# MCORD_SAS_BNC.net
KiCad netlist of a schematic drawn in Altium Designer
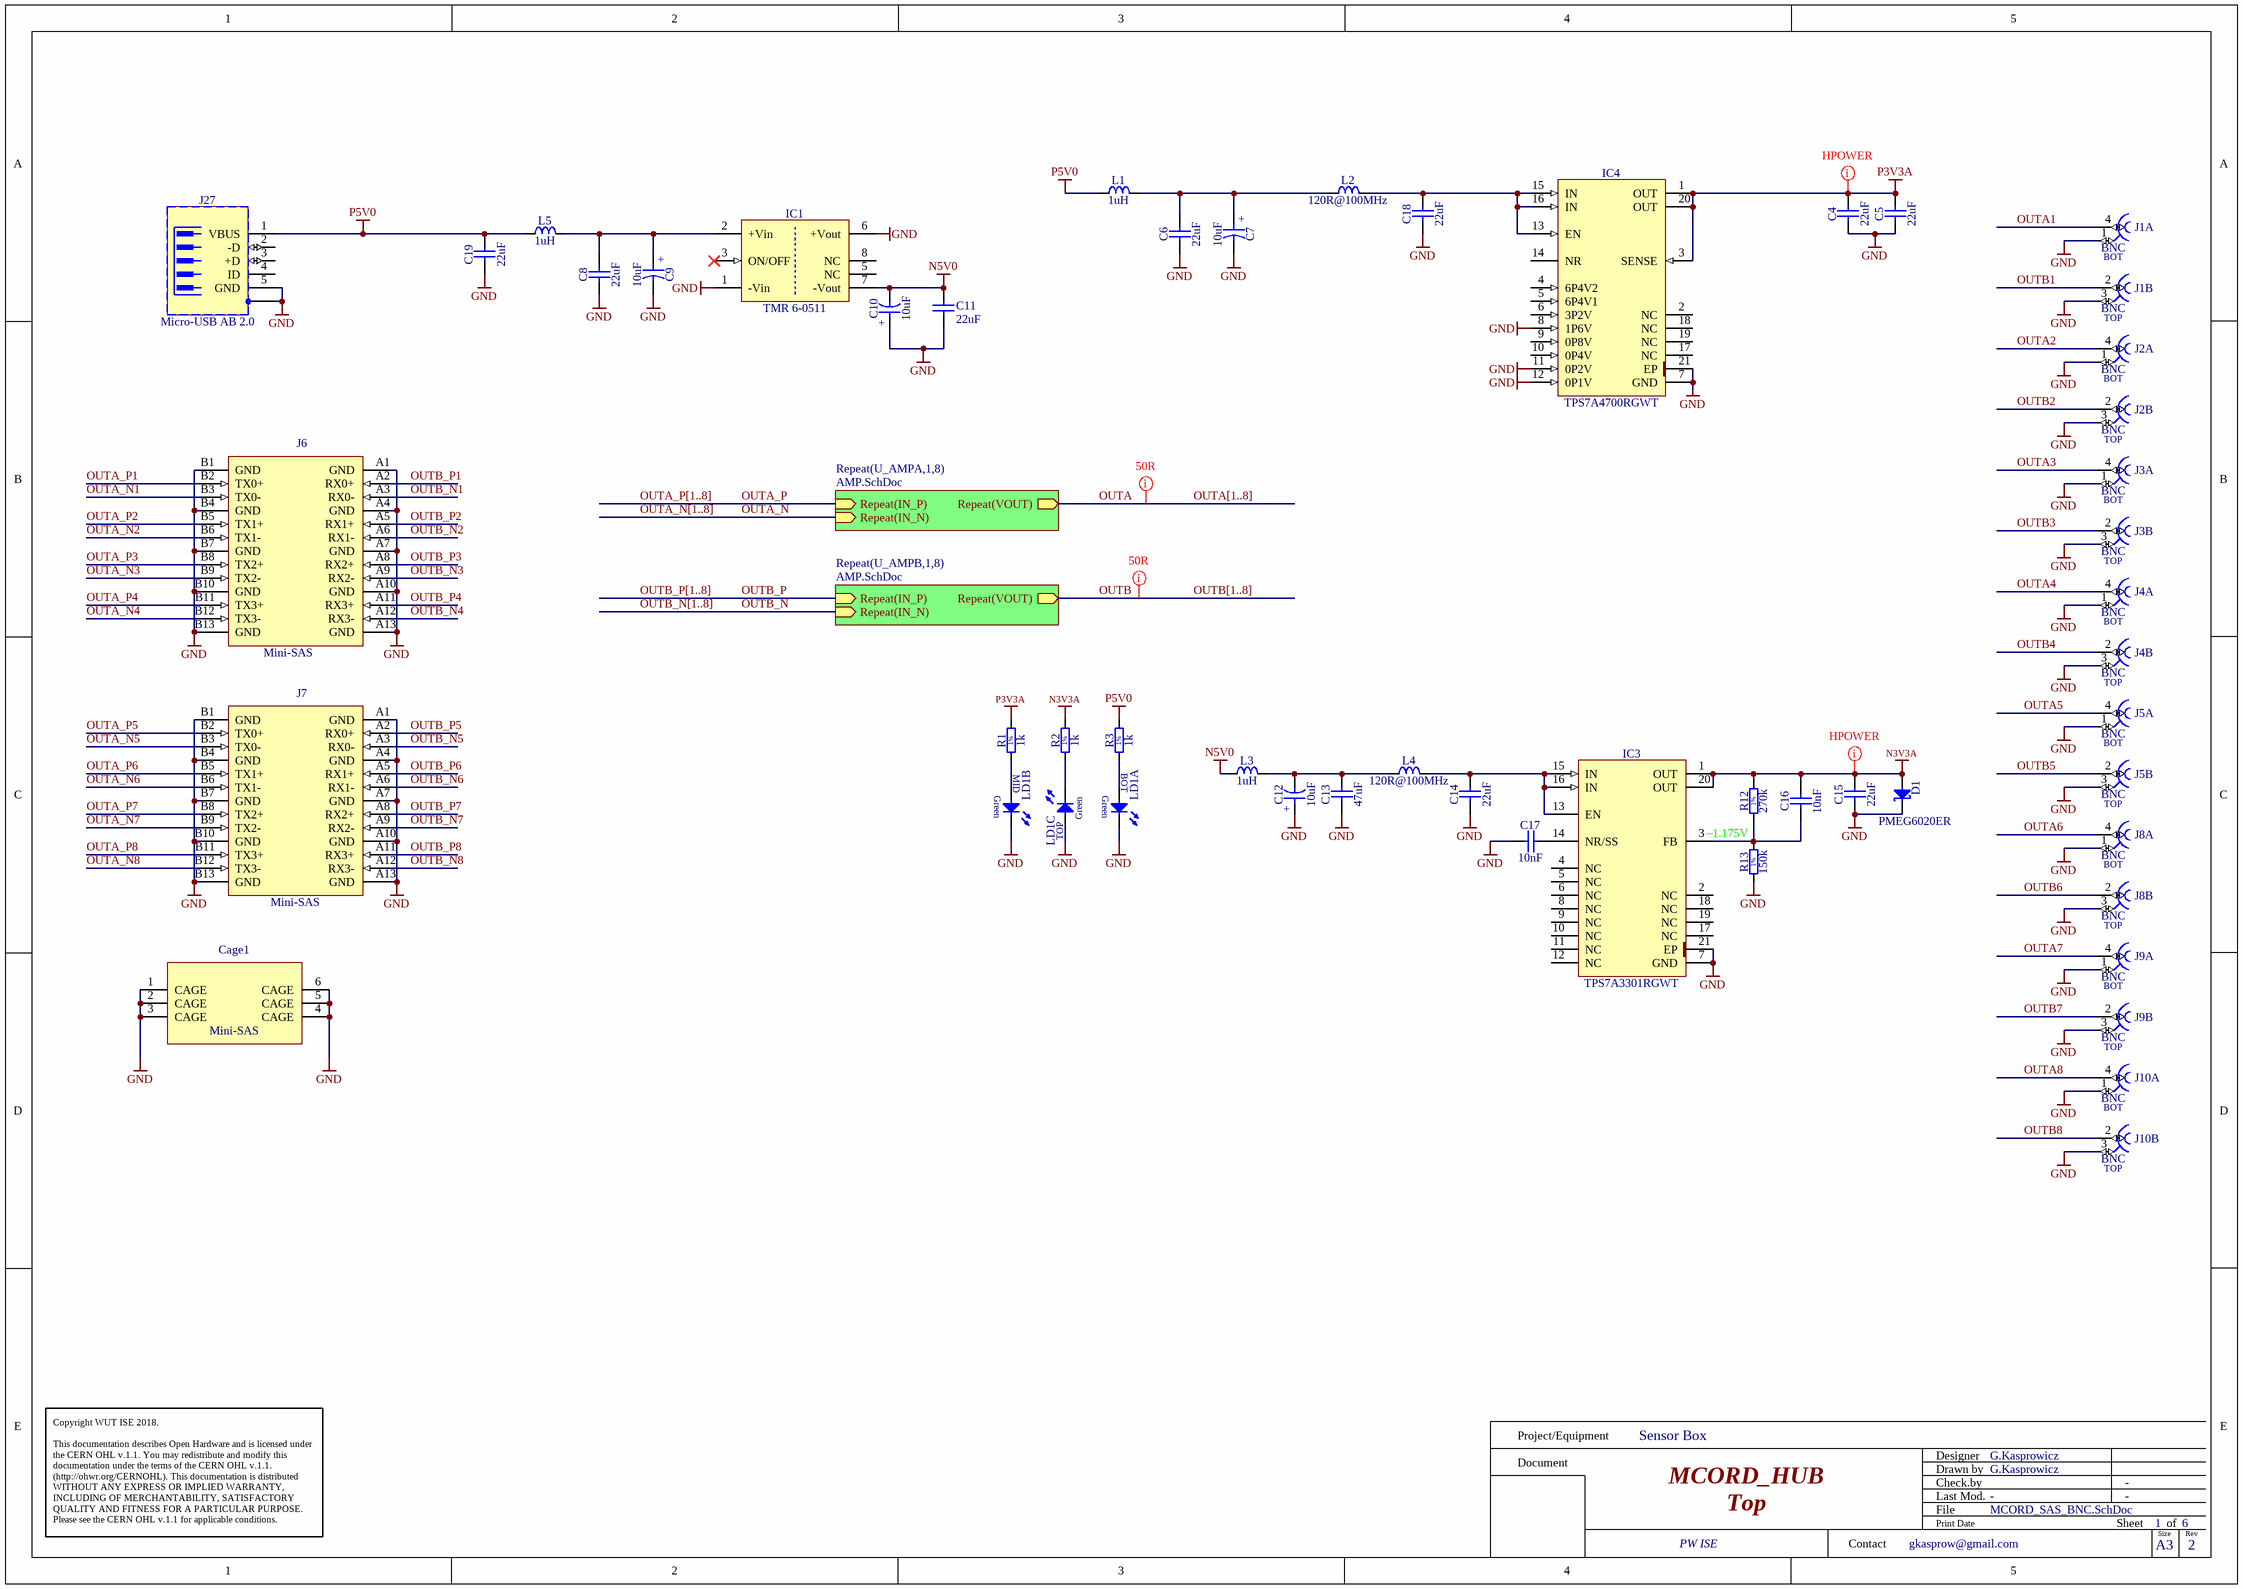
[diagram p0: MCORD_SAS_BNC.SchDoc]

(export (version "E")
  (design (tool "Eeschema 10.0.6"))
  (components
    (comp (ref "C4")
      (value "22uF")
      (footprint "CAPC2012X135N")
      (description "Non-polarised capacitor")
      (fields
        (field (name "PART NUMBER") "CC0805_22UF_16V_10%_X5R")
        (field (name "VOLTAGE") "16V")
        (field (name "AUTHOR") "CERN DEM JLC")
      )
      (libsource (lib "Capacitors") (part "Capacitor - non polarized"))
    )
    (comp (ref "C5")
      (value "22uF")
      (footprint "CAPC2012X135N")
      (description "Non-polarised capacitor")
      (fields
        (field (name "PART NUMBER") "CC0805_22UF_16V_10%_X5R")
        (field (name "VOLTAGE") "16V")
        (field (name "AUTHOR") "CERN DEM JLC")
      )
      (libsource (lib "Capacitors") (part "Capacitor - non polarized"))
    )
    (comp (ref "C6")
      (value "22uF")
      (footprint "CAPC2012X135N")
      (description "Non-polarised capacitor")
      (fields
        (field (name "PART NUMBER") "CC0805_22UF_16V_10%_X5R")
        (field (name "VOLTAGE") "16V")
        (field (name "AUTHOR") "CERN DEM JLC")
      )
      (libsource (lib "Capacitors") (part "Capacitor - non polarized"))
    )
    (comp (ref "C7")
      (value "10uF")
      (footprint "CAPMP3216X180N")
      (description "Polarised capacitor")
      (fields
        (field (name "PART NUMBER") "CTE3216-18_10UF_10V_10%_LESR1800")
        (field (name "VOLTAGE") "10V")
        (field (name "AUTHOR") "CERN DEM JLC")
      )
      (libsource (lib "Capacitors") (part "Capacitor - polarized"))
    )
    (comp (ref "C8")
      (value "22uF")
      (footprint "CAPC2012X135N")
      (description "Non-polarised capacitor")
      (fields
        (field (name "PART NUMBER") "CC0805_22UF_16V_10%_X5R")
        (field (name "VOLTAGE") "16V")
        (field (name "AUTHOR") "CERN DEM JLC")
      )
      (libsource (lib "Capacitors") (part "Capacitor - non polarized"))
    )
    (comp (ref "C9")
      (value "10uF")
      (footprint "CAPMP3216X180N")
      (description "Polarised capacitor")
      (fields
        (field (name "PART NUMBER") "CTE3216-18_10UF_10V_10%_LESR1800")
        (field (name "VOLTAGE") "10V")
        (field (name "AUTHOR") "CERN DEM JLC")
      )
      (libsource (lib "Capacitors") (part "Capacitor - polarized"))
    )
    (comp (ref "C10")
      (value "10uF")
      (footprint "CAPMP3216X180N")
      (description "Polarised capacitor")
      (fields
        (field (name "PART NUMBER") "CTE3216-18_10UF_10V_10%_LESR1800")
        (field (name "VOLTAGE") "10V")
        (field (name "AUTHOR") "CERN DEM JLC")
      )
      (libsource (lib "Capacitors") (part "Capacitor - polarized"))
    )
    (comp (ref "C11")
      (value "22uF")
      (footprint "CAPC2012X135N")
      (description "Non-polarised capacitor")
      (fields
        (field (name "PART NUMBER") "CC0805_22UF_16V_10%_X5R")
        (field (name "VOLTAGE") "16V")
        (field (name "AUTHOR") "CERN DEM JLC")
      )
      (libsource (lib "Capacitors") (part "Capacitor - non polarized"))
    )
    (comp (ref "C12")
      (value "10uF")
      (footprint "CAPMP3216X180N")
      (description "Polarised capacitor")
      (fields
        (field (name "PART NUMBER") "CTE3216-18_10UF_10V_10%_LESR1800")
        (field (name "VOLTAGE") "10V")
        (field (name "AUTHOR") "CERN DEM JLC")
      )
      (libsource (lib "Capacitors") (part "Capacitor - polarized"))
    )
    (comp (ref "C13")
      (value "47uF")
      (footprint "CAPC2012X140N")
      (description "Non-polarised capacitor")
      (fields
        (field (name "PART NUMBER") "CC0805_47UF_6.3V_20%_X5R")
        (field (name "VOLTAGE") "6.3V")
        (field (name "AUTHOR") "CERN DEM JLC")
      )
      (libsource (lib "Capacitors") (part "Capacitor - non polarized"))
    )
    (comp (ref "C14")
      (value "22uF")
      (footprint "CAPC2012X135N")
      (description "Non-polarised capacitor")
      (fields
        (field (name "PART NUMBER") "CC0805_22UF_16V_10%_X5R")
        (field (name "VOLTAGE") "16V")
        (field (name "AUTHOR") "CERN DEM JLC")
      )
      (libsource (lib "Capacitors") (part "Capacitor - non polarized"))
    )
    (comp (ref "C15")
      (value "22uF")
      (footprint "CAPC2012X135N")
      (description "Non-polarised capacitor")
      (fields
        (field (name "PART NUMBER") "CC0805_22UF_16V_10%_X5R")
        (field (name "VOLTAGE") "16V")
        (field (name "AUTHOR") "CERN DEM JLC")
      )
      (libsource (lib "Capacitors") (part "Capacitor - non polarized"))
    )
    (comp (ref "C16")
      (value "10nF")
      (footprint "CAPC1608X87N")
      (description "Non-polarised capacitor")
      (fields
        (field (name "PART NUMBER") "CC0603_10NF_50V_10%_X7R")
        (field (name "VOLTAGE") "50V")
        (field (name "AUTHOR") "CERN DEM JLC")
      )
      (libsource (lib "Capacitors") (part "Capacitor - non polarized"))
    )
    (comp (ref "C17")
      (value "10nF")
      (footprint "CAPC1608X87N")
      (description "Non-polarised capacitor")
      (fields
        (field (name "PART NUMBER") "CC0603_10NF_50V_10%_X7R")
        (field (name "VOLTAGE") "50V")
        (field (name "AUTHOR") "CERN DEM JLC")
      )
      (libsource (lib "Capacitors") (part "Capacitor - non polarized"))
    )
    (comp (ref "C18")
      (value "22uF")
      (footprint "CAPC2012X135N")
      (description "Non-polarised capacitor")
      (fields
        (field (name "PART NUMBER") "CC0805_22UF_16V_10%_X5R")
        (field (name "VOLTAGE") "16V")
        (field (name "AUTHOR") "CERN DEM JLC")
      )
      (libsource (lib "Capacitors") (part "Capacitor - non polarized"))
    )
    (comp (ref "C19")
      (value "22uF")
      (footprint "CAPC2012X135N")
      (description "Non-polarised capacitor")
      (fields
        (field (name "PART NUMBER") "CC0805_22UF_16V_10%_X5R")
        (field (name "VOLTAGE") "16V")
        (field (name "AUTHOR") "CERN DEM JLC")
      )
      (libsource (lib "Capacitors") (part "Capacitor - non polarized"))
    )
    (comp (ref "Cage1")
      (value "Mini-SAS")
      (footprint "TYCO_1888321-2")
      (description "Mini-SAS Cage (6Pins)")
      (fields
        (field (name "PART NUMBER") "TYCO_1888321-2")
        (field (name "MANUFACTURER") "TYCO ELECTRONICS")
        (field (name "AUTHOR") "CERN DEM BC")
      )
      (libsource (lib "Connectors") (part "Mini-SAS Cage (6Pins)"))
    )
    (comp (ref "D1")
      (value "PMEG6020ER")
      (footprint "SODFL3517X110N")
      (description "Schottky Diode")
      (fields
        (field (name "VOLTAGE") "60V")
        (field (name "POWER") "2A")
        (field (name "AUTHOR") "CERN DEM JMW")
      )
      (libsource (lib "ICs And Semiconductors") (part "Diode Schottky"))
    )
    (comp (ref "IC1")
      (value "TMR 6-0511")
      (footprint "DCDC_TRACO_TMR6")
      (description "TRACO, TMR Series, Single Output DCDC Converter")
      (fields (field (name "MANUFACTURER") "TRACO POWER") (field (name "AUTHOR") "CERN DEM MR"))
      (libsource (lib "ICs And Semiconductors") (part "DCDC_TRACO_TMR_Single Output"))
    )
    (comp (ref "IC3")
      (value "TPS7A3301RGWT")
      (footprint "QFN65P500X500X100-21N-S325")
      (description "-1.18V to -33V -1A, Ultra-Low Noise, High PSRR, Low-Dropout Linear Regulator")
      (fields (field (name "MANUFACTURER") "TEXAS INSTRUMENTS") (field (name "AUTHOR") "CERN DEM JLC"))
      (libsource (lib "ICs And Semiconductors") (part "TPS7A3301RGW"))
    )
    (comp (ref "IC4")
      (value "TPS7A4700RGWT")
      (footprint "QFN65P500X500X100-21N-S325")
      (description "Low Noise (3uVrms), 1A, High Voltage Low-Dropout Linear Regulator")
      (fields (field (name "MANUFACTURER") "TEXAS INSTRUMENTS") (field (name "AUTHOR") "CERN DEM JLC"))
      (libsource (lib "ICs And Semiconductors") (part "TPS7A4700RGW"))
    )
    (comp (ref "J1")
      (value "BNC")
      (footprint "BOMAR_364A2595")
      (description "Dual Right Angle 50 Ohm BNC Jack, White Valox Case")
      (fields
        (field (name "PART NUMBER") "BOMAR_364A2595")
        (field (name "MANUFACTURER") "BOMAR INTERCONNECT")
        (field (name "AUTHOR") "CERN DEM JLC")
      )
      (libsource (lib "Connectors") (part "BOMAR_364A2595"))
    )
    (comp (ref "J2")
      (value "BNC")
      (footprint "BOMAR_364A2595")
      (description "Dual Right Angle 50 Ohm BNC Jack, White Valox Case")
      (fields
        (field (name "PART NUMBER") "BOMAR_364A2595")
        (field (name "MANUFACTURER") "BOMAR INTERCONNECT")
        (field (name "AUTHOR") "CERN DEM JLC")
      )
      (libsource (lib "Connectors") (part "BOMAR_364A2595"))
    )
    (comp (ref "J3")
      (value "BNC")
      (footprint "BOMAR_364A2595")
      (description "Dual Right Angle 50 Ohm BNC Jack, White Valox Case")
      (fields
        (field (name "PART NUMBER") "BOMAR_364A2595")
        (field (name "MANUFACTURER") "BOMAR INTERCONNECT")
        (field (name "AUTHOR") "CERN DEM JLC")
      )
      (libsource (lib "Connectors") (part "BOMAR_364A2595"))
    )
    (comp (ref "J4")
      (value "BNC")
      (footprint "BOMAR_364A2595")
      (description "Dual Right Angle 50 Ohm BNC Jack, White Valox Case")
      (fields
        (field (name "PART NUMBER") "BOMAR_364A2595")
        (field (name "MANUFACTURER") "BOMAR INTERCONNECT")
        (field (name "AUTHOR") "CERN DEM JLC")
      )
      (libsource (lib "Connectors") (part "BOMAR_364A2595"))
    )
    (comp (ref "J5")
      (value "BNC")
      (footprint "BOMAR_364A2595")
      (description "Dual Right Angle 50 Ohm BNC Jack, White Valox Case")
      (fields
        (field (name "PART NUMBER") "BOMAR_364A2595")
        (field (name "MANUFACTURER") "BOMAR INTERCONNECT")
        (field (name "AUTHOR") "CERN DEM JLC")
      )
      (libsource (lib "Connectors") (part "BOMAR_364A2595"))
    )
    (comp (ref "J6")
      (value "Mini-SAS")
      (footprint "TYCO_1761987-7")
      (description "26 Position Mini-Sas Connector (Quad Small Form-Factor SFF-8088)")
      (fields
        (field (name "PART NUMBER") "TYCO_1761987-7")
        (field (name "MANUFACTURER") "TYCO ELECTRONICS")
        (field (name "AUTHOR") "CERN DEM MR")
      )
      (libsource (lib "Connectors") (part "Mini-SAS"))
    )
    (comp (ref "J7")
      (value "Mini-SAS")
      (footprint "TYCO_1761987-7")
      (description "26 Position Mini-Sas Connector (Quad Small Form-Factor SFF-8088)")
      (fields
        (field (name "PART NUMBER") "TYCO_1761987-7")
        (field (name "MANUFACTURER") "TYCO ELECTRONICS")
        (field (name "AUTHOR") "CERN DEM MR")
      )
      (libsource (lib "Connectors") (part "Mini-SAS"))
    )
    (comp (ref "J8")
      (value "BNC")
      (footprint "BOMAR_364A2595")
      (description "Dual Right Angle 50 Ohm BNC Jack, White Valox Case")
      (fields
        (field (name "PART NUMBER") "BOMAR_364A2595")
        (field (name "MANUFACTURER") "BOMAR INTERCONNECT")
        (field (name "AUTHOR") "CERN DEM JLC")
      )
      (libsource (lib "Connectors") (part "BOMAR_364A2595"))
    )
    (comp (ref "J9")
      (value "BNC")
      (footprint "BOMAR_364A2595")
      (description "Dual Right Angle 50 Ohm BNC Jack, White Valox Case")
      (fields
        (field (name "PART NUMBER") "BOMAR_364A2595")
        (field (name "MANUFACTURER") "BOMAR INTERCONNECT")
        (field (name "AUTHOR") "CERN DEM JLC")
      )
      (libsource (lib "Connectors") (part "BOMAR_364A2595"))
    )
    (comp (ref "J10")
      (value "BNC")
      (footprint "BOMAR_364A2595")
      (description "Dual Right Angle 50 Ohm BNC Jack, White Valox Case")
      (fields
        (field (name "PART NUMBER") "BOMAR_364A2595")
        (field (name "MANUFACTURER") "BOMAR INTERCONNECT")
        (field (name "AUTHOR") "CERN DEM JLC")
      )
      (libsource (lib "Connectors") (part "BOMAR_364A2595"))
    )
    (comp (ref "J27")
      (value "Micro-USB AB 2.0")
      (footprint "HIROSE_ZX62RD-AB-5P8(30)")
      (description "5 Pin + 1 Shield USB Receptacle")
      (fields
        (field (name "PART NUMBER") "HIROSE_ZX62RD-AB-5P8(30)")
        (field (name "MANUFACTURER") "HIROSE (HRS)")
        (field (name "AUTHOR") "CERN DEM JMW")
      )
      (libsource (lib "Connectors") (part "Connector USB 5 Pin + 1Shield"))
    )
    (comp (ref "L1")
      (value "1uH")
      (footprint "INDC2620X100N")
      (description "Inductor")
      (fields
        (field (name "PART NUMBER") "IND1008_1UH_20%_WURTH_74479787210B")
        (field (name "POWER") "1.95A")
        (field (name "AUTHOR") "CERN DEM JLC")
      )
      (libsource (lib "Inductors & Transformers") (part "Inductor"))
    )
    (comp (ref "L2")
      (value "120R@100MHz")
      (footprint "INDC1608X65N")
      (description "Inductor")
      (fields
        (field (name "PART NUMBER") "IND0603_MURATA_BLM18SG121TN1D")
        (field (name "POWER") "3A")
        (field (name "AUTHOR") "CERN DEM JLC")
      )
      (libsource (lib "Inductors & Transformers") (part "Inductor"))
    )
    (comp (ref "L3")
      (value "1uH")
      (footprint "INDC2620X100N")
      (description "Inductor")
      (fields
        (field (name "PART NUMBER") "IND1008_1UH_20%_WURTH_74479787210B")
        (field (name "POWER") "1.95A")
        (field (name "AUTHOR") "CERN DEM JLC")
      )
      (libsource (lib "Inductors & Transformers") (part "Inductor"))
    )
    (comp (ref "L4")
      (value "120R@100MHz")
      (footprint "INDC1608X65N")
      (description "Inductor")
      (fields
        (field (name "PART NUMBER") "IND0603_MURATA_BLM18SG121TN1D")
        (field (name "POWER") "3A")
        (field (name "AUTHOR") "CERN DEM JLC")
      )
      (libsource (lib "Inductors & Transformers") (part "Inductor"))
    )
    (comp (ref "L5")
      (value "1uH")
      (footprint "INDC2620X100N")
      (description "Inductor")
      (fields
        (field (name "PART NUMBER") "IND1008_1UH_20%_WURTH_74479787210B")
        (field (name "POWER") "1.95A")
        (field (name "AUTHOR") "CERN DEM JLC")
      )
      (libsource (lib "Inductors & Transformers") (part "Inductor"))
    )
    (comp (ref "LD1")
      (value "Green/Green/Green")
      (footprint "LED_DIALIGHT_570-0100-222F")
      (description "LED x3 Green LED")
      (fields
        (field (name "PART NUMBER") "LED_DIALIGHT_570-0100-222F")
        (field (name "MANUFACTURER") "DIALIGHT")
        (field (name "AUTHOR") "CERN DEM JLC")
      )
      (libsource (lib "ICs And Semiconductors") (part "LED x3 G-1A2C-BOT_G-3A4C_G-5A6C-TOP"))
    )
    (comp (ref "R1")
      (value "1k")
      (footprint "RESC1608X55N")
      (description "Resistor - 1%")
      (fields
        (field (name "PART NUMBER") "R0603_1K_1%_0.1W_100PPM")
        (field (name "POWER") "0.1W")
        (field (name "AUTHOR") "CERN DEM JLC")
      )
      (libsource (lib "Resistors") (part "Resistor - 1%"))
    )
    (comp (ref "R2")
      (value "1k")
      (footprint "RESC1608X55N")
      (description "Resistor - 1%")
      (fields
        (field (name "PART NUMBER") "R0603_1K_1%_0.1W_100PPM")
        (field (name "POWER") "0.1W")
        (field (name "AUTHOR") "CERN DEM JLC")
      )
      (libsource (lib "Resistors") (part "Resistor - 1%"))
    )
    (comp (ref "R3")
      (value "1k")
      (footprint "RESC1608X55N")
      (description "Resistor - 1%")
      (fields
        (field (name "PART NUMBER") "R0603_1K_1%_0.1W_100PPM")
        (field (name "POWER") "0.1W")
        (field (name "AUTHOR") "CERN DEM JLC")
      )
      (libsource (lib "Resistors") (part "Resistor - 1%"))
    )
    (comp (ref "R12")
      (value "270k")
      (footprint "RESC1608X55N")
      (description "Resistor - 1%")
      (fields
        (field (name "PART NUMBER") "R0603_270K_1%_0.1W_100PPM")
        (field (name "POWER") "0.1W")
        (field (name "AUTHOR") "CERN DEM JLC")
      )
      (libsource (lib "Resistors") (part "Resistor - 1%"))
    )
    (comp (ref "R13")
      (value "150k")
      (footprint "RESC1608X55N")
      (description "Resistor - 1%")
      (fields
        (field (name "PART NUMBER") "R0603_150K_1%_0.1W_100PPM")
        (field (name "POWER") "0.1W")
        (field (name "AUTHOR") "CERN DEM JLC")
      )
      (libsource (lib "Resistors") (part "Resistor - 1%"))
    )
  )
  (nets
    (net (code "2") (name "/OUTA1") (class "Default")
      (node (ref "J1") (pin "4") (pinfunction "4_4") (pintype "bidirectional"))
    )
    (net (code "3") (name "/OUTA2") (class "Default")
      (node (ref "J2") (pin "4") (pinfunction "4_4") (pintype "bidirectional"))
    )
    (net (code "4") (name "/OUTA3") (class "Default")
      (node (ref "J3") (pin "4") (pinfunction "4_4") (pintype "bidirectional"))
    )
    (net (code "5") (name "/OUTA4") (class "Default")
      (node (ref "J4") (pin "4") (pinfunction "4_4") (pintype "bidirectional"))
    )
    (net (code "6") (name "/OUTA5") (class "Default")
      (node (ref "J5") (pin "4") (pinfunction "4_4") (pintype "bidirectional"))
    )
    (net (code "7") (name "/OUTA6") (class "Default")
      (node (ref "J8") (pin "4") (pinfunction "4_4") (pintype "bidirectional"))
    )
    (net (code "8") (name "/OUTA7") (class "Default")
      (node (ref "J9") (pin "4") (pinfunction "4_4") (pintype "bidirectional"))
    )
    (net (code "9") (name "/OUTA8") (class "Default")
      (node (ref "J10") (pin "4") (pinfunction "4_4") (pintype "bidirectional"))
    )
    (net (code "12") (name "/OUTA_N1") (class "Default")
      (node (ref "J6") (pin "B3") (pinfunction "TX0-_B3") (pintype "input"))
    )
    (net (code "13") (name "/OUTA_N2") (class "Default")
      (node (ref "J6") (pin "B6") (pinfunction "TX1-_B6") (pintype "input"))
    )
    (net (code "14") (name "/OUTA_N3") (class "Default")
      (node (ref "J6") (pin "B9") (pinfunction "TX2-_B9") (pintype "input"))
    )
    (net (code "15") (name "/OUTA_N4") (class "Default")
      (node (ref "J6") (pin "B12") (pinfunction "TX3-_B12") (pintype "input"))
    )
    (net (code "16") (name "/OUTA_N5") (class "Default")
      (node (ref "J7") (pin "B3") (pinfunction "TX0-_B3") (pintype "input"))
    )
    (net (code "17") (name "/OUTA_N6") (class "Default")
      (node (ref "J7") (pin "B6") (pinfunction "TX1-_B6") (pintype "input"))
    )
    (net (code "18") (name "/OUTA_N7") (class "Default")
      (node (ref "J7") (pin "B9") (pinfunction "TX2-_B9") (pintype "input"))
    )
    (net (code "19") (name "/OUTA_N8") (class "Default")
      (node (ref "J7") (pin "B12") (pinfunction "TX3-_B12") (pintype "input"))
    )
    (net (code "22") (name "/OUTA_P1") (class "Default")
      (node (ref "J6") (pin "B2") (pinfunction "TX0+_B2") (pintype "input"))
    )
    (net (code "23") (name "/OUTA_P2") (class "Default")
      (node (ref "J6") (pin "B5") (pinfunction "TX1+_B5") (pintype "input"))
    )
    (net (code "24") (name "/OUTA_P3") (class "Default")
      (node (ref "J6") (pin "B8") (pinfunction "TX2+_B8") (pintype "input"))
    )
    (net (code "25") (name "/OUTA_P4") (class "Default")
      (node (ref "J6") (pin "B11") (pinfunction "TX3+_B11") (pintype "input"))
    )
    (net (code "26") (name "/OUTA_P5") (class "Default")
      (node (ref "J7") (pin "B2") (pinfunction "TX0+_B2") (pintype "input"))
    )
    (net (code "27") (name "/OUTA_P6") (class "Default")
      (node (ref "J7") (pin "B5") (pinfunction "TX1+_B5") (pintype "input"))
    )
    (net (code "28") (name "/OUTA_P7") (class "Default")
      (node (ref "J7") (pin "B8") (pinfunction "TX2+_B8") (pintype "input"))
    )
    (net (code "29") (name "/OUTA_P8") (class "Default")
      (node (ref "J7") (pin "B11") (pinfunction "TX3+_B11") (pintype "input"))
    )
    (net (code "32") (name "/OUTB1") (class "Default")
      (node (ref "J1") (pin "2") (pinfunction "2_2") (pintype "bidirectional"))
    )
    (net (code "33") (name "/OUTB2") (class "Default")
      (node (ref "J2") (pin "2") (pinfunction "2_2") (pintype "bidirectional"))
    )
    (net (code "34") (name "/OUTB3") (class "Default")
      (node (ref "J3") (pin "2") (pinfunction "2_2") (pintype "bidirectional"))
    )
    (net (code "35") (name "/OUTB4") (class "Default")
      (node (ref "J4") (pin "2") (pinfunction "2_2") (pintype "bidirectional"))
    )
    (net (code "36") (name "/OUTB5") (class "Default")
      (node (ref "J5") (pin "2") (pinfunction "2_2") (pintype "bidirectional"))
    )
    (net (code "37") (name "/OUTB6") (class "Default")
      (node (ref "J8") (pin "2") (pinfunction "2_2") (pintype "bidirectional"))
    )
    (net (code "38") (name "/OUTB7") (class "Default")
      (node (ref "J9") (pin "2") (pinfunction "2_2") (pintype "bidirectional"))
    )
    (net (code "39") (name "/OUTB8") (class "Default")
      (node (ref "J10") (pin "2") (pinfunction "2_2") (pintype "bidirectional"))
    )
    (net (code "42") (name "/OUTB_N1") (class "Default")
      (node (ref "J6") (pin "A3") (pinfunction "RX0-_A3") (pintype "input"))
    )
    (net (code "43") (name "/OUTB_N2") (class "Default")
      (node (ref "J6") (pin "A6") (pinfunction "RX1-_A6") (pintype "input"))
    )
    (net (code "44") (name "/OUTB_N3") (class "Default")
      (node (ref "J6") (pin "A9") (pinfunction "RX2-_A9") (pintype "input"))
    )
    (net (code "45") (name "/OUTB_N4") (class "Default")
      (node (ref "J6") (pin "A12") (pinfunction "RX3-_A12") (pintype "input"))
    )
    (net (code "46") (name "/OUTB_N5") (class "Default")
      (node (ref "J7") (pin "A3") (pinfunction "RX0-_A3") (pintype "input"))
    )
    (net (code "47") (name "/OUTB_N6") (class "Default")
      (node (ref "J7") (pin "A6") (pinfunction "RX1-_A6") (pintype "input"))
    )
    (net (code "48") (name "/OUTB_N7") (class "Default")
      (node (ref "J7") (pin "A9") (pinfunction "RX2-_A9") (pintype "input"))
    )
    (net (code "49") (name "/OUTB_N8") (class "Default")
      (node (ref "J7") (pin "A12") (pinfunction "RX3-_A12") (pintype "input"))
    )
    (net (code "52") (name "/OUTB_P1") (class "Default")
      (node (ref "J6") (pin "A2") (pinfunction "RX0+_A2") (pintype "input"))
    )
    (net (code "53") (name "/OUTB_P2") (class "Default")
      (node (ref "J6") (pin "A5") (pinfunction "RX1+_A5") (pintype "input"))
    )
    (net (code "54") (name "/OUTB_P3") (class "Default")
      (node (ref "J6") (pin "A8") (pinfunction "RX2+_A8") (pintype "input"))
    )
    (net (code "55") (name "/OUTB_P4") (class "Default")
      (node (ref "J6") (pin "A11") (pinfunction "RX3+_A11") (pintype "input"))
    )
    (net (code "56") (name "/OUTB_P5") (class "Default")
      (node (ref "J7") (pin "A2") (pinfunction "RX0+_A2") (pintype "input"))
    )
    (net (code "57") (name "/OUTB_P6") (class "Default")
      (node (ref "J7") (pin "A5") (pinfunction "RX1+_A5") (pintype "input"))
    )
    (net (code "58") (name "/OUTB_P7") (class "Default")
      (node (ref "J7") (pin "A8") (pinfunction "RX2+_A8") (pintype "input"))
    )
    (net (code "59") (name "/OUTB_P8") (class "Default")
      (node (ref "J7") (pin "A11") (pinfunction "RX3+_A11") (pintype "input"))
    )
    (net (code "61") (name "GND") (class "Default")
      (node (ref "C10") (pin "1") (pinfunction "1_1") (pintype "passive"))
      (node (ref "C11") (pin "2") (pinfunction "2_2") (pintype "passive"))
      (node (ref "C12") (pin "1") (pinfunction "1_1") (pintype "passive"))
      (node (ref "C13") (pin "1") (pinfunction "1_1") (pintype "passive"))
      (node (ref "C14") (pin "1") (pinfunction "1_1") (pintype "passive"))
      (node (ref "C15") (pin "1") (pinfunction "1_1") (pintype "passive"))
      (node (ref "C17") (pin "1") (pinfunction "1_1") (pintype "passive"))
      (node (ref "C18") (pin "1") (pinfunction "1_1") (pintype "passive"))
      (node (ref "C19") (pin "1") (pinfunction "1_1") (pintype "passive"))
      (node (ref "C4") (pin "1") (pinfunction "1_1") (pintype "passive"))
      (node (ref "C5") (pin "1") (pinfunction "1_1") (pintype "passive"))
      (node (ref "C6") (pin "1") (pinfunction "1_1") (pintype "passive"))
      (node (ref "C7") (pin "2") (pinfunction "2_2") (pintype "passive"))
      (node (ref "C8") (pin "1") (pinfunction "1_1") (pintype "passive"))
      (node (ref "C9") (pin "2") (pinfunction "2_2") (pintype "passive"))
      (node (ref "Cage1") (pin "1") (pinfunction "CAGE_1") (pintype "power_in"))
      (node (ref "Cage1") (pin "2") (pinfunction "CAGE_2") (pintype "power_in"))
      (node (ref "Cage1") (pin "3") (pinfunction "CAGE_3") (pintype "power_in"))
      (node (ref "Cage1") (pin "4") (pinfunction "CAGE_4") (pintype "power_in"))
      (node (ref "Cage1") (pin "5") (pinfunction "CAGE_5") (pintype "power_in"))
      (node (ref "Cage1") (pin "6") (pinfunction "CAGE_6") (pintype "power_in"))
      (node (ref "D1") (pin "1") (pinfunction "C_1") (pintype "passive"))
      (node (ref "IC1") (pin "1") (pinfunction "-Vin_1") (pintype "power_in"))
      (node (ref "IC1") (pin "6") (pinfunction "+Vout_6") (pintype "power_in"))
      (node (ref "IC3") (pin "21") (pinfunction "EP_21") (pintype "power_in"))
      (node (ref "IC3") (pin "7") (pinfunction "GND_7") (pintype "power_in"))
      (node (ref "IC4") (pin "11") (pinfunction "0P2V_11") (pintype "input"))
      (node (ref "IC4") (pin "12") (pinfunction "0P1V_12") (pintype "input"))
      (node (ref "IC4") (pin "21") (pinfunction "EP_21") (pintype "power_in"))
      (node (ref "IC4") (pin "7") (pinfunction "GND_7") (pintype "power_in"))
      (node (ref "IC4") (pin "8") (pinfunction "1P6V_8") (pintype "input"))
      (node (ref "J1") (pin "1") (pinfunction "1_1") (pintype "bidirectional"))
      (node (ref "J1") (pin "3") (pinfunction "3_3") (pintype "bidirectional"))
      (node (ref "J10") (pin "1") (pinfunction "1_1") (pintype "bidirectional"))
      (node (ref "J10") (pin "3") (pinfunction "3_3") (pintype "bidirectional"))
      (node (ref "J2") (pin "1") (pinfunction "1_1") (pintype "bidirectional"))
      (node (ref "J2") (pin "3") (pinfunction "3_3") (pintype "bidirectional"))
      (node (ref "J27") (pin "5") (pinfunction "GND_5") (pintype "power_in"))
      (node (ref "J27") (pin "6") (pinfunction "SH_6") (pintype "power_in"))
      (node (ref "J3") (pin "1") (pinfunction "1_1") (pintype "bidirectional"))
      (node (ref "J3") (pin "3") (pinfunction "3_3") (pintype "bidirectional"))
      (node (ref "J4") (pin "1") (pinfunction "1_1") (pintype "bidirectional"))
      (node (ref "J4") (pin "3") (pinfunction "3_3") (pintype "bidirectional"))
      (node (ref "J5") (pin "1") (pinfunction "1_1") (pintype "bidirectional"))
      (node (ref "J5") (pin "3") (pinfunction "3_3") (pintype "bidirectional"))
      (node (ref "J6") (pin "A1") (pinfunction "GND_A1") (pintype "power_in"))
      (node (ref "J6") (pin "A10") (pinfunction "GND_A10") (pintype "power_in"))
      (node (ref "J6") (pin "A13") (pinfunction "GND_A13") (pintype "power_in"))
      (node (ref "J6") (pin "A4") (pinfunction "GND_A4") (pintype "power_in"))
      (node (ref "J6") (pin "A7") (pinfunction "GND_A7") (pintype "power_in"))
      (node (ref "J6") (pin "B1") (pinfunction "GND_B1") (pintype "power_in"))
      (node (ref "J6") (pin "B10") (pinfunction "GND_B10") (pintype "power_in"))
      (node (ref "J6") (pin "B13") (pinfunction "GND_B13") (pintype "power_in"))
      (node (ref "J6") (pin "B4") (pinfunction "GND_B4") (pintype "power_in"))
      (node (ref "J6") (pin "B7") (pinfunction "GND_B7") (pintype "power_in"))
      (node (ref "J7") (pin "A1") (pinfunction "GND_A1") (pintype "power_in"))
      (node (ref "J7") (pin "A10") (pinfunction "GND_A10") (pintype "power_in"))
      (node (ref "J7") (pin "A13") (pinfunction "GND_A13") (pintype "power_in"))
      (node (ref "J7") (pin "A4") (pinfunction "GND_A4") (pintype "power_in"))
      (node (ref "J7") (pin "A7") (pinfunction "GND_A7") (pintype "power_in"))
      (node (ref "J7") (pin "B1") (pinfunction "GND_B1") (pintype "power_in"))
      (node (ref "J7") (pin "B10") (pinfunction "GND_B10") (pintype "power_in"))
      (node (ref "J7") (pin "B13") (pinfunction "GND_B13") (pintype "power_in"))
      (node (ref "J7") (pin "B4") (pinfunction "GND_B4") (pintype "power_in"))
      (node (ref "J7") (pin "B7") (pinfunction "GND_B7") (pintype "power_in"))
      (node (ref "J8") (pin "1") (pinfunction "1_1") (pintype "bidirectional"))
      (node (ref "J8") (pin "3") (pinfunction "3_3") (pintype "bidirectional"))
      (node (ref "J9") (pin "1") (pinfunction "1_1") (pintype "bidirectional"))
      (node (ref "J9") (pin "3") (pinfunction "3_3") (pintype "bidirectional"))
      (node (ref "LD1") (pin "2") (pinfunction "C_2") (pintype "passive"))
      (node (ref "LD1") (pin "4") (pinfunction "C_4") (pintype "passive"))
      (node (ref "LD1") (pin "5") (pinfunction "A_5") (pintype "passive"))
      (node (ref "R13") (pin "1") (pinfunction "1_1") (pintype "passive"))
    )
    (net (code "62") (name "N3V3A") (class "Default")
      (node (ref "C15") (pin "2") (pinfunction "2_2") (pintype "passive"))
      (node (ref "C16") (pin "2") (pinfunction "2_2") (pintype "passive"))
      (node (ref "D1") (pin "2") (pinfunction "A_2") (pintype "passive"))
      (node (ref "IC3") (pin "1") (pinfunction "OUT_1") (pintype "power_in"))
      (node (ref "IC3") (pin "20") (pinfunction "OUT_20") (pintype "power_in"))
      (node (ref "R12") (pin "2") (pinfunction "2_2") (pintype "passive"))
      (node (ref "R2") (pin "2") (pinfunction "2_2") (pintype "passive"))
    )
    (net (code "63") (name "N5V0") (class "Default")
      (node (ref "C10") (pin "2") (pinfunction "2_2") (pintype "passive"))
      (node (ref "C11") (pin "1") (pinfunction "1_1") (pintype "passive"))
      (node (ref "IC1") (pin "7") (pinfunction "-Vout_7") (pintype "power_in"))
      (node (ref "L3") (pin "1") (pinfunction "1_1") (pintype "passive"))
    )
    (net (code "64") (name "Net-(C6-Pad2)") (class "Default")
      (node (ref "C6") (pin "2") (pinfunction "2_2") (pintype "passive"))
      (node (ref "C7") (pin "1") (pinfunction "1_1") (pintype "passive"))
      (node (ref "L1") (pin "2") (pinfunction "2_2") (pintype "passive"))
      (node (ref "L2") (pin "1") (pinfunction "1_1") (pintype "passive"))
    )
    (net (code "65") (name "Net-(C12-Pad2)") (class "Default")
      (node (ref "C12") (pin "2") (pinfunction "2_2") (pintype "passive"))
      (node (ref "C13") (pin "2") (pinfunction "2_2") (pintype "passive"))
      (node (ref "L3") (pin "2") (pinfunction "2_2") (pintype "passive"))
      (node (ref "L4") (pin "1") (pinfunction "1_1") (pintype "passive"))
    )
    (net (code "66") (name "Net-(IC1-+Vin)") (class "Default")
      (node (ref "C8") (pin "2") (pinfunction "2_2") (pintype "passive"))
      (node (ref "C9") (pin "1") (pinfunction "1_1") (pintype "passive"))
      (node (ref "IC1") (pin "2") (pinfunction "+Vin_2") (pintype "power_in"))
      (node (ref "L5") (pin "2") (pinfunction "2_2") (pintype "passive"))
    )
    (net (code "67") (name "Net-(IC3-EN)") (class "Default")
      (node (ref "C14") (pin "2") (pinfunction "2_2") (pintype "passive"))
      (node (ref "IC3") (pin "13") (pinfunction "EN_13") (pintype "passive"))
      (node (ref "IC3") (pin "15") (pinfunction "IN_15") (pintype "input"))
      (node (ref "IC3") (pin "16") (pinfunction "IN_16") (pintype "input"))
      (node (ref "L4") (pin "2") (pinfunction "2_2") (pintype "passive"))
    )
    (net (code "68") (name "Net-(IC3-FB)") (class "Default")
      (node (ref "C16") (pin "1") (pinfunction "1_1") (pintype "passive"))
      (node (ref "IC3") (pin "3") (pinfunction "FB_3") (pintype "passive"))
      (node (ref "R12") (pin "1") (pinfunction "1_1") (pintype "passive"))
      (node (ref "R13") (pin "2") (pinfunction "2_2") (pintype "passive"))
    )
    (net (code "69") (name "Net-(IC3-NR{slash}SS)") (class "Default")
      (node (ref "C17") (pin "2") (pinfunction "2_2") (pintype "passive"))
      (node (ref "IC3") (pin "14") (pinfunction "NR/SS_14") (pintype "passive"))
    )
    (net (code "70") (name "Net-(IC4-EN)") (class "Default")
      (node (ref "C18") (pin "2") (pinfunction "2_2") (pintype "passive"))
      (node (ref "IC4") (pin "13") (pinfunction "EN_13") (pintype "input"))
      (node (ref "IC4") (pin "15") (pinfunction "IN_15") (pintype "input"))
      (node (ref "IC4") (pin "16") (pinfunction "IN_16") (pintype "input"))
      (node (ref "L2") (pin "2") (pinfunction "2_2") (pintype "passive"))
    )
    (net (code "71") (name "Net-(LD1A-A)") (class "Default")
      (node (ref "LD1") (pin "1") (pinfunction "A_1") (pintype "passive"))
      (node (ref "R3") (pin "1") (pinfunction "1_1") (pintype "passive"))
    )
    (net (code "72") (name "Net-(LD1B-A)") (class "Default")
      (node (ref "LD1") (pin "3") (pinfunction "A_3") (pintype "passive"))
      (node (ref "R1") (pin "1") (pinfunction "1_1") (pintype "passive"))
    )
    (net (code "73") (name "Net-(LD1C-C)") (class "Default")
      (node (ref "LD1") (pin "6") (pinfunction "C_6") (pintype "passive"))
      (node (ref "R2") (pin "1") (pinfunction "1_1") (pintype "passive"))
    )
    (net (code "74") (name "P3V3A") (class "Default")
      (node (ref "C4") (pin "2") (pinfunction "2_2") (pintype "passive"))
      (node (ref "C5") (pin "2") (pinfunction "2_2") (pintype "passive"))
      (node (ref "IC4") (pin "1") (pinfunction "OUT_1") (pintype "power_in"))
      (node (ref "IC4") (pin "20") (pinfunction "OUT_20") (pintype "power_in"))
      (node (ref "IC4") (pin "3") (pinfunction "SENSE_3") (pintype "input"))
      (node (ref "R1") (pin "2") (pinfunction "2_2") (pintype "passive"))
    )
    (net (code "75") (name "P5V0") (class "Default")
      (node (ref "C19") (pin "2") (pinfunction "2_2") (pintype "passive"))
      (node (ref "J27") (pin "1") (pinfunction "VBUS_1") (pintype "power_in"))
      (node (ref "L1") (pin "1") (pinfunction "1_1") (pintype "passive"))
      (node (ref "L5") (pin "1") (pinfunction "1_1") (pintype "passive"))
      (node (ref "R3") (pin "2") (pinfunction "2_2") (pintype "passive"))
    )
    (net (code "76") (name "unconnected-(IC1-NC-Pad5)") (class "Default")
      (node (ref "IC1") (pin "5") (pinfunction "NC_5") (pintype "passive"))
    )
    (net (code "77") (name "unconnected-(IC1-NC-Pad8)") (class "Default")
      (node (ref "IC1") (pin "8") (pinfunction "NC_8") (pintype "passive"))
    )
    (net (code "78") (name "unconnected-(IC1-ON{slash}OFF-Pad3)") (class "Default")
      (node (ref "IC1") (pin "3") (pinfunction "ON/OFF_3") (pintype "input+no_connect"))
    )
    (net (code "79") (name "unconnected-(IC3-NC-Pad2)") (class "Default")
      (node (ref "IC3") (pin "2") (pinfunction "NC_2") (pintype "passive"))
    )
    (net (code "80") (name "unconnected-(IC3-NC-Pad4)") (class "Default")
      (node (ref "IC3") (pin "4") (pinfunction "NC_4") (pintype "passive"))
    )
    (net (code "81") (name "unconnected-(IC3-NC-Pad5)") (class "Default")
      (node (ref "IC3") (pin "5") (pinfunction "NC_5") (pintype "passive"))
    )
    (net (code "82") (name "unconnected-(IC3-NC-Pad6)") (class "Default")
      (node (ref "IC3") (pin "6") (pinfunction "NC_6") (pintype "passive"))
    )
    (net (code "83") (name "unconnected-(IC3-NC-Pad8)") (class "Default")
      (node (ref "IC3") (pin "8") (pinfunction "NC_8") (pintype "passive"))
    )
    (net (code "84") (name "unconnected-(IC3-NC-Pad9)") (class "Default")
      (node (ref "IC3") (pin "9") (pinfunction "NC_9") (pintype "passive"))
    )
    (net (code "85") (name "unconnected-(IC3-NC-Pad10)") (class "Default")
      (node (ref "IC3") (pin "10") (pinfunction "NC_10") (pintype "passive"))
    )
    (net (code "86") (name "unconnected-(IC3-NC-Pad11)") (class "Default")
      (node (ref "IC3") (pin "11") (pinfunction "NC_11") (pintype "passive"))
    )
    (net (code "87") (name "unconnected-(IC3-NC-Pad12)") (class "Default")
      (node (ref "IC3") (pin "12") (pinfunction "NC_12") (pintype "passive"))
    )
    (net (code "88") (name "unconnected-(IC3-NC-Pad17)") (class "Default")
      (node (ref "IC3") (pin "17") (pinfunction "NC_17") (pintype "passive"))
    )
    (net (code "89") (name "unconnected-(IC3-NC-Pad18)") (class "Default")
      (node (ref "IC3") (pin "18") (pinfunction "NC_18") (pintype "passive"))
    )
    (net (code "90") (name "unconnected-(IC3-NC-Pad19)") (class "Default")
      (node (ref "IC3") (pin "19") (pinfunction "NC_19") (pintype "passive"))
    )
    (net (code "91") (name "unconnected-(IC4-0P4V-Pad10)") (class "Default")
      (node (ref "IC4") (pin "10") (pinfunction "0P4V_10") (pintype "input"))
    )
    (net (code "92") (name "unconnected-(IC4-0P8V-Pad9)") (class "Default")
      (node (ref "IC4") (pin "9") (pinfunction "0P8V_9") (pintype "input"))
    )
    (net (code "93") (name "unconnected-(IC4-3P2V-Pad6)") (class "Default")
      (node (ref "IC4") (pin "6") (pinfunction "3P2V_6") (pintype "input"))
    )
    (net (code "94") (name "unconnected-(IC4-6P4V1-Pad5)") (class "Default")
      (node (ref "IC4") (pin "5") (pinfunction "6P4V1_5") (pintype "input"))
    )
    (net (code "95") (name "unconnected-(IC4-6P4V2-Pad4)") (class "Default")
      (node (ref "IC4") (pin "4") (pinfunction "6P4V2_4") (pintype "input"))
    )
    (net (code "96") (name "unconnected-(IC4-NC-Pad2)") (class "Default")
      (node (ref "IC4") (pin "2") (pinfunction "NC_2") (pintype "passive"))
    )
    (net (code "97") (name "unconnected-(IC4-NC-Pad17)") (class "Default")
      (node (ref "IC4") (pin "17") (pinfunction "NC_17") (pintype "passive"))
    )
    (net (code "98") (name "unconnected-(IC4-NC-Pad18)") (class "Default")
      (node (ref "IC4") (pin "18") (pinfunction "NC_18") (pintype "passive"))
    )
    (net (code "99") (name "unconnected-(IC4-NC-Pad19)") (class "Default")
      (node (ref "IC4") (pin "19") (pinfunction "NC_19") (pintype "passive"))
    )
    (net (code "100") (name "unconnected-(IC4-NR-Pad14)") (class "Default")
      (node (ref "IC4") (pin "14") (pinfunction "NR_14") (pintype "passive"))
    )
    (net (code "101") (name "unconnected-(J27-+D-Pad3)") (class "Default")
      (node (ref "J27") (pin "3") (pinfunction "+D_3") (pintype "bidirectional"))
    )
    (net (code "102") (name "unconnected-(J27--D-Pad2)") (class "Default")
      (node (ref "J27") (pin "2") (pinfunction "-D_2") (pintype "bidirectional"))
    )
    (net (code "103") (name "unconnected-(J27-ID-Pad4)") (class "Default")
      (node (ref "J27") (pin "4") (pinfunction "ID_4") (pintype "passive"))
    )
  )
)
